# MCU.net
KiCad netlist of a schematic drawn in Altium Designer
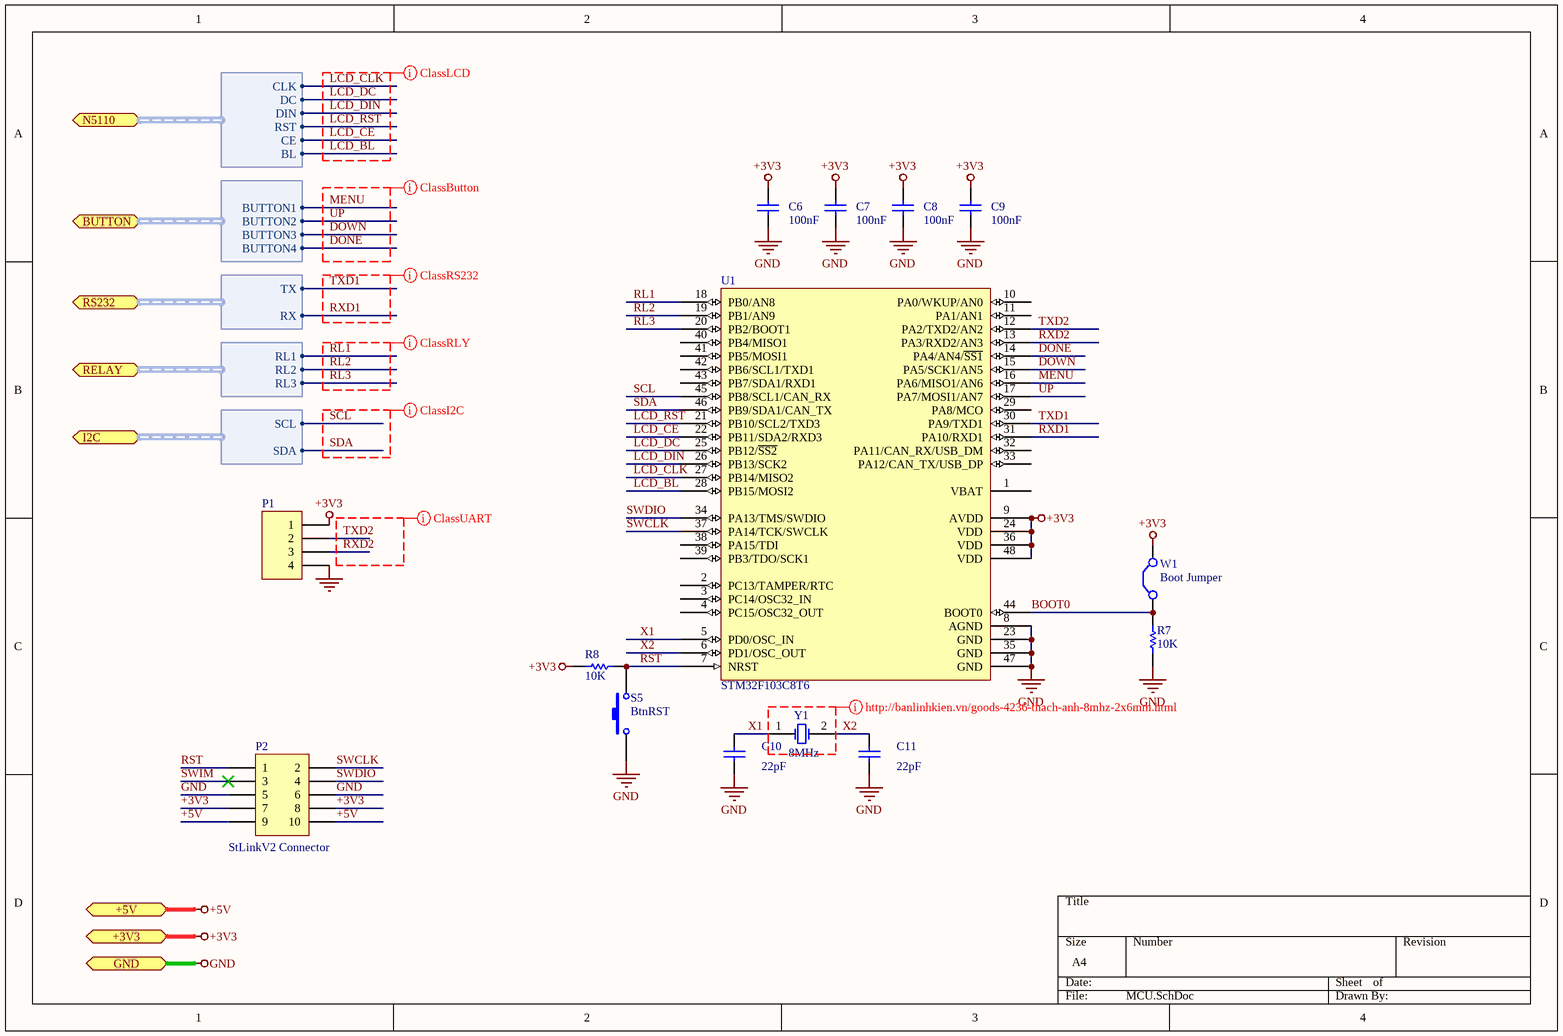
[diagram p0: MCU.SchDoc]

(export (version "E")
  (design (tool "Eeschema 10.0.6"))
  (components
    (comp (ref "C6")
      (value "100nF")
      (footprint "C-0805")
      (description "Capacitor")
      (fields (field (name "Comment") "104") (field (name "PUBLISHER") "Altium Limited"))
      (libsource (lib "Miscellaneous Devices") (part "Cap"))
    )
    (comp (ref "C7")
      (value "100nF")
      (footprint "C-0805")
      (description "Capacitor")
      (fields (field (name "Comment") "104") (field (name "PUBLISHER") "Altium Limited"))
      (libsource (lib "Miscellaneous Devices") (part "Cap"))
    )
    (comp (ref "C8")
      (value "100nF")
      (footprint "C-0805")
      (description "Capacitor")
      (fields (field (name "Comment") "104") (field (name "PUBLISHER") "Altium Limited"))
      (libsource (lib "Miscellaneous Devices") (part "Cap"))
    )
    (comp (ref "C9")
      (value "100nF")
      (footprint "C-0805")
      (description "Capacitor")
      (fields (field (name "Comment") "104") (field (name "PUBLISHER") "Altium Limited"))
      (libsource (lib "Miscellaneous Devices") (part "Cap"))
    )
    (comp (ref "C10")
      (value "22pF")
      (footprint "C-0805")
      (description "Capacitor")
      (fields (field (name "Comment") "22") (field (name "PUBLISHER") "Altium Limited"))
      (libsource (lib "Miscellaneous Devices") (part "Cap"))
    )
    (comp (ref "C11")
      (value "22pF")
      (footprint "C-0805")
      (description "Capacitor")
      (fields (field (name "Comment") "22") (field (name "PUBLISHER") "Altium Limited"))
      (libsource (lib "Miscellaneous Devices") (part "Cap"))
    )
    (comp (ref "P1")
      (value "XH2.54-4P")
      (footprint "CONN-XH2.54-4P")
      (description "Header, 4-Pin")
      (libsource (lib "Miscellaneous Connectors") (part "Header 4"))
    )
    (comp (ref "P2")
      (value "StLinkV2 Connector")
      (footprint "CONN-IDC-5X2-A")
      (description "Header, 5-Pin, Dual row")
      (fields (field (name "Comment") "IDC5x2A"))
      (libsource (lib "Miscellaneous Connectors") (part "Header 5X2"))
    )
    (comp (ref "R7")
      (value "10K")
      (footprint "R-0805")
      (description "Resistor")
      (fields (field (name "PUBLISHER") "Altium Limited"))
      (libsource (lib "Miscellaneous Devices") (part "Res1"))
    )
    (comp (ref "R8")
      (value "10K")
      (footprint "R-0805")
      (description "Resistor")
      (fields (field (name "PUBLISHER") "Altium Limited"))
      (libsource (lib "Miscellaneous Devices") (part "Res1"))
    )
    (comp (ref "S5")
      (value "BtnRST")
      (footprint "SW-T-S6")
      (description "Switch")
      (fields (field (name "Comment") "SW-T-S6"))
      (libsource (lib "Miscellaneous Devices") (part "SW-PB"))
    )
    (comp (ref "U1")
      (value "STM32F103C8T6")
      (footprint "LQFP-48")
      (description "32bits STM32 48 Pins")
      (libsource (lib "Dlib") (part "STM32F103C8T6"))
    )
    (comp (ref "W1")
      (value "Boot Jumper")
      (footprint "JP2.54-M-1x02A")
      (description "Jumper Wire")
      (fields (field (name "Comment") "JP2.54-M"))
      (libsource (lib "Miscellaneous Devices") (part "Jumper"))
    )
    (comp (ref "Y1")
      (value "8MHz")
      (footprint "R38")
      (description "Crystal Oscillator")
      (fields (field (name "Comment") "49S-8MHz"))
      (libsource (lib "Miscellaneous Devices") (part "XTAL"))
    )
  )
  (nets
    (net (code "6") (name "+3V3") (class "Default")
      (node (ref "C6") (pin "1") (pinfunction "1_1") (pintype "passive"))
      (node (ref "C7") (pin "1") (pinfunction "1_1") (pintype "passive"))
      (node (ref "C8") (pin "1") (pinfunction "1_1") (pintype "passive"))
      (node (ref "C9") (pin "1") (pinfunction "1_1") (pintype "passive"))
      (node (ref "P1") (pin "1") (pinfunction "1_1") (pintype "passive"))
      (node (ref "P2") (pin "7") (pinfunction "7_7") (pintype "passive"))
      (node (ref "P2") (pin "8") (pinfunction "8_8") (pintype "passive"))
      (node (ref "R8") (pin "2") (pinfunction "2_2") (pintype "passive"))
      (node (ref "U1") (pin "24") (pinfunction "VDD_24") (pintype "power_in"))
      (node (ref "U1") (pin "36") (pinfunction "VDD_36") (pintype "power_in"))
      (node (ref "U1") (pin "48") (pinfunction "VDD_48") (pintype "power_in"))
      (node (ref "U1") (pin "9") (pinfunction "AVDD_9") (pintype "power_in"))
      (node (ref "W1") (pin "2") (pinfunction "C2_2") (pintype "passive"))
    )
    (net (code "7") (name "+5V") (class "Default")
      (node (ref "P2") (pin "10") (pinfunction "10_10") (pintype "passive"))
      (node (ref "P2") (pin "9") (pinfunction "9_9") (pintype "passive"))
    )
    (net (code "8") (name "/BOOT0") (class "Default")
      (node (ref "R7") (pin "1") (pinfunction "1_1") (pintype "passive"))
      (node (ref "U1") (pin "44") (pinfunction "BOOT0_44") (pintype "bidirectional"))
      (node (ref "W1") (pin "1") (pinfunction "C1_1") (pintype "passive"))
    )
    (net (code "9") (name "/DONE") (class "Default")
      (node (ref "U1") (pin "14") (pinfunction "PA4/AN4/~{SS1}_14") (pintype "bidirectional"))
    )
    (net (code "10") (name "/DOWN") (class "Default")
      (node (ref "U1") (pin "15") (pinfunction "PA5/SCK1/AN5_15") (pintype "bidirectional"))
    )
    (net (code "11") (name "/LCD_BL") (class "Default")
      (node (ref "U1") (pin "28") (pinfunction "PB15/MOSI2_28") (pintype "bidirectional"))
    )
    (net (code "12") (name "/LCD_CE") (class "Default")
      (node (ref "U1") (pin "22") (pinfunction "PB11/SDA2/RXD3_22") (pintype "bidirectional"))
    )
    (net (code "13") (name "/LCD_CLK") (class "Default")
      (node (ref "U1") (pin "27") (pinfunction "PB14/MISO2_27") (pintype "bidirectional"))
    )
    (net (code "14") (name "/LCD_DC") (class "Default")
      (node (ref "U1") (pin "25") (pinfunction "PB12/~{SS2}_25") (pintype "bidirectional"))
    )
    (net (code "15") (name "/LCD_DIN") (class "Default")
      (node (ref "U1") (pin "26") (pinfunction "PB13/SCK2_26") (pintype "bidirectional"))
    )
    (net (code "16") (name "/LCD_RST") (class "Default")
      (node (ref "U1") (pin "21") (pinfunction "PB10/SCL2/TXD3_21") (pintype "bidirectional"))
    )
    (net (code "17") (name "/MENU") (class "Default")
      (node (ref "U1") (pin "16") (pinfunction "PA6/MISO1/AN6_16") (pintype "bidirectional"))
    )
    (net (code "18") (name "/RL1") (class "Default")
      (node (ref "U1") (pin "18") (pinfunction "PB0/AN8_18") (pintype "bidirectional"))
    )
    (net (code "19") (name "/RL2") (class "Default")
      (node (ref "U1") (pin "19") (pinfunction "PB1/AN9_19") (pintype "bidirectional"))
    )
    (net (code "20") (name "/RL3") (class "Default")
      (node (ref "U1") (pin "20") (pinfunction "PB2/BOOT1_20") (pintype "bidirectional"))
    )
    (net (code "21") (name "/RST") (class "Default")
      (node (ref "P2") (pin "1") (pinfunction "1_1") (pintype "passive"))
      (node (ref "R8") (pin "1") (pinfunction "1_1") (pintype "passive"))
      (node (ref "S5") (pin "2") (pinfunction "2_2") (pintype "passive"))
      (node (ref "U1") (pin "7") (pinfunction "NRST_7") (pintype "input"))
    )
    (net (code "22") (name "/RXD1") (class "Default")
      (node (ref "U1") (pin "31") (pinfunction "PA10/RXD1_31") (pintype "bidirectional"))
    )
    (net (code "23") (name "/RXD2") (class "Default")
      (node (ref "P1") (pin "3") (pinfunction "3_3") (pintype "passive"))
      (node (ref "U1") (pin "13") (pinfunction "PA3/RXD2/AN3_13") (pintype "bidirectional"))
    )
    (net (code "24") (name "/SCL") (class "Default")
      (node (ref "U1") (pin "45") (pinfunction "PB8/SCL1/CAN_RX_45") (pintype "bidirectional"))
    )
    (net (code "25") (name "/SDA") (class "Default")
      (node (ref "U1") (pin "46") (pinfunction "PB9/SDA1/CAN_TX_46") (pintype "bidirectional"))
    )
    (net (code "26") (name "/SWCLK") (class "Default")
      (node (ref "P2") (pin "2") (pinfunction "2_2") (pintype "passive"))
      (node (ref "U1") (pin "37") (pinfunction "PA14/TCK/SWCLK_37") (pintype "bidirectional"))
    )
    (net (code "27") (name "/SWDIO") (class "Default")
      (node (ref "P2") (pin "4") (pinfunction "4_4") (pintype "passive"))
      (node (ref "U1") (pin "34") (pinfunction "PA13/TMS/SWDIO_34") (pintype "bidirectional"))
    )
    (net (code "28") (name "/SWIM") (class "Default")
      (node (ref "P2") (pin "3") (pinfunction "3_3") (pintype "passive+no_connect"))
    )
    (net (code "29") (name "/TXD1") (class "Default")
      (node (ref "U1") (pin "30") (pinfunction "PA9/TXD1_30") (pintype "bidirectional"))
    )
    (net (code "30") (name "/TXD2") (class "Default")
      (node (ref "P1") (pin "2") (pinfunction "2_2") (pintype "passive"))
      (node (ref "U1") (pin "12") (pinfunction "PA2/TXD2/AN2_12") (pintype "bidirectional"))
    )
    (net (code "31") (name "/UP") (class "Default")
      (node (ref "U1") (pin "17") (pinfunction "PA7/MOSI1/AN7_17") (pintype "bidirectional"))
    )
    (net (code "32") (name "/X1") (class "Default")
      (node (ref "C10") (pin "1") (pinfunction "1_1") (pintype "passive"))
      (node (ref "U1") (pin "5") (pinfunction "PD0/OSC_IN_5") (pintype "bidirectional"))
      (node (ref "Y1") (pin "1") (pinfunction "OSC1_1") (pintype "passive"))
    )
    (net (code "33") (name "/X2") (class "Default")
      (node (ref "C11") (pin "1") (pinfunction "1_1") (pintype "passive"))
      (node (ref "U1") (pin "6") (pinfunction "PD1/OSC_OUT_6") (pintype "bidirectional"))
      (node (ref "Y1") (pin "2") (pinfunction "OSC2_2") (pintype "passive"))
    )
    (net (code "39") (name "GND") (class "Default")
      (node (ref "C10") (pin "2") (pinfunction "2_2") (pintype "passive"))
      (node (ref "C11") (pin "2") (pinfunction "2_2") (pintype "passive"))
      (node (ref "C6") (pin "2") (pinfunction "2_2") (pintype "passive"))
      (node (ref "C7") (pin "2") (pinfunction "2_2") (pintype "passive"))
      (node (ref "C8") (pin "2") (pinfunction "2_2") (pintype "passive"))
      (node (ref "C9") (pin "2") (pinfunction "2_2") (pintype "passive"))
      (node (ref "P1") (pin "4") (pinfunction "4_4") (pintype "passive"))
      (node (ref "P2") (pin "5") (pinfunction "5_5") (pintype "passive"))
      (node (ref "P2") (pin "6") (pinfunction "6_6") (pintype "passive"))
      (node (ref "R7") (pin "2") (pinfunction "2_2") (pintype "passive"))
      (node (ref "S5") (pin "1") (pinfunction "1_1") (pintype "passive"))
      (node (ref "U1") (pin "23") (pinfunction "GND_23") (pintype "power_in"))
      (node (ref "U1") (pin "35") (pinfunction "GND_35") (pintype "power_in"))
      (node (ref "U1") (pin "47") (pinfunction "GND_47") (pintype "power_in"))
      (node (ref "U1") (pin "8") (pinfunction "AGND_8") (pintype "power_in"))
    )
    (net (code "40") (name "unconnected-(U1-PA0{slash}WKUP{slash}AN0-Pad10)") (class "Default")
      (node (ref "U1") (pin "10") (pinfunction "PA0/WKUP/AN0_10") (pintype "bidirectional"))
    )
    (net (code "41") (name "unconnected-(U1-PA1{slash}AN1-Pad11)") (class "Default")
      (node (ref "U1") (pin "11") (pinfunction "PA1/AN1_11") (pintype "bidirectional"))
    )
    (net (code "42") (name "unconnected-(U1-PA8{slash}MCO-Pad29)") (class "Default")
      (node (ref "U1") (pin "29") (pinfunction "PA8/MCO_29") (pintype "bidirectional"))
    )
    (net (code "43") (name "unconnected-(U1-PA11{slash}CAN_RX{slash}USB_DM-Pad32)") (class "Default")
      (node (ref "U1") (pin "32") (pinfunction "PA11/CAN_RX/USB_DM_32") (pintype "bidirectional"))
    )
    (net (code "44") (name "unconnected-(U1-PA12{slash}CAN_TX{slash}USB_DP-Pad33)") (class "Default")
      (node (ref "U1") (pin "33") (pinfunction "PA12/CAN_TX/USB_DP_33") (pintype "bidirectional"))
    )
    (net (code "45") (name "unconnected-(U1-PA15{slash}TDI-Pad38)") (class "Default")
      (node (ref "U1") (pin "38") (pinfunction "PA15/TDI_38") (pintype "bidirectional"))
    )
    (net (code "46") (name "unconnected-(U1-PB3{slash}TDO{slash}SCK1-Pad39)") (class "Default")
      (node (ref "U1") (pin "39") (pinfunction "PB3/TDO/SCK1_39") (pintype "bidirectional"))
    )
    (net (code "47") (name "unconnected-(U1-PB4{slash}MISO1-Pad40)") (class "Default")
      (node (ref "U1") (pin "40") (pinfunction "PB4/MISO1_40") (pintype "bidirectional"))
    )
    (net (code "48") (name "unconnected-(U1-PB5{slash}MOSI1-Pad41)") (class "Default")
      (node (ref "U1") (pin "41") (pinfunction "PB5/MOSI1_41") (pintype "bidirectional"))
    )
    (net (code "49") (name "unconnected-(U1-PB6{slash}SCL1{slash}TXD1-Pad42)") (class "Default")
      (node (ref "U1") (pin "42") (pinfunction "PB6/SCL1/TXD1_42") (pintype "bidirectional"))
    )
    (net (code "50") (name "unconnected-(U1-PB7{slash}SDA1{slash}RXD1-Pad43)") (class "Default")
      (node (ref "U1") (pin "43") (pinfunction "PB7/SDA1/RXD1_43") (pintype "bidirectional"))
    )
    (net (code "51") (name "unconnected-(U1-PC13{slash}TAMPER{slash}RTC-Pad2)") (class "Default")
      (node (ref "U1") (pin "2") (pinfunction "PC13/TAMPER/RTC_2") (pintype "bidirectional"))
    )
    (net (code "52") (name "unconnected-(U1-PC14{slash}OSC32_IN-Pad3)") (class "Default")
      (node (ref "U1") (pin "3") (pinfunction "PC14/OSC32_IN_3") (pintype "bidirectional"))
    )
    (net (code "53") (name "unconnected-(U1-PC15{slash}OSC32_OUT-Pad4)") (class "Default")
      (node (ref "U1") (pin "4") (pinfunction "PC15/OSC32_OUT_4") (pintype "bidirectional"))
    )
    (net (code "54") (name "unconnected-(U1-VBAT-Pad1)") (class "Default")
      (node (ref "U1") (pin "1") (pinfunction "VBAT_1") (pintype "power_in"))
    )
  )
)
